# Sensor_Overview.net
KiCad netlist of a schematic drawn in Altium Designer
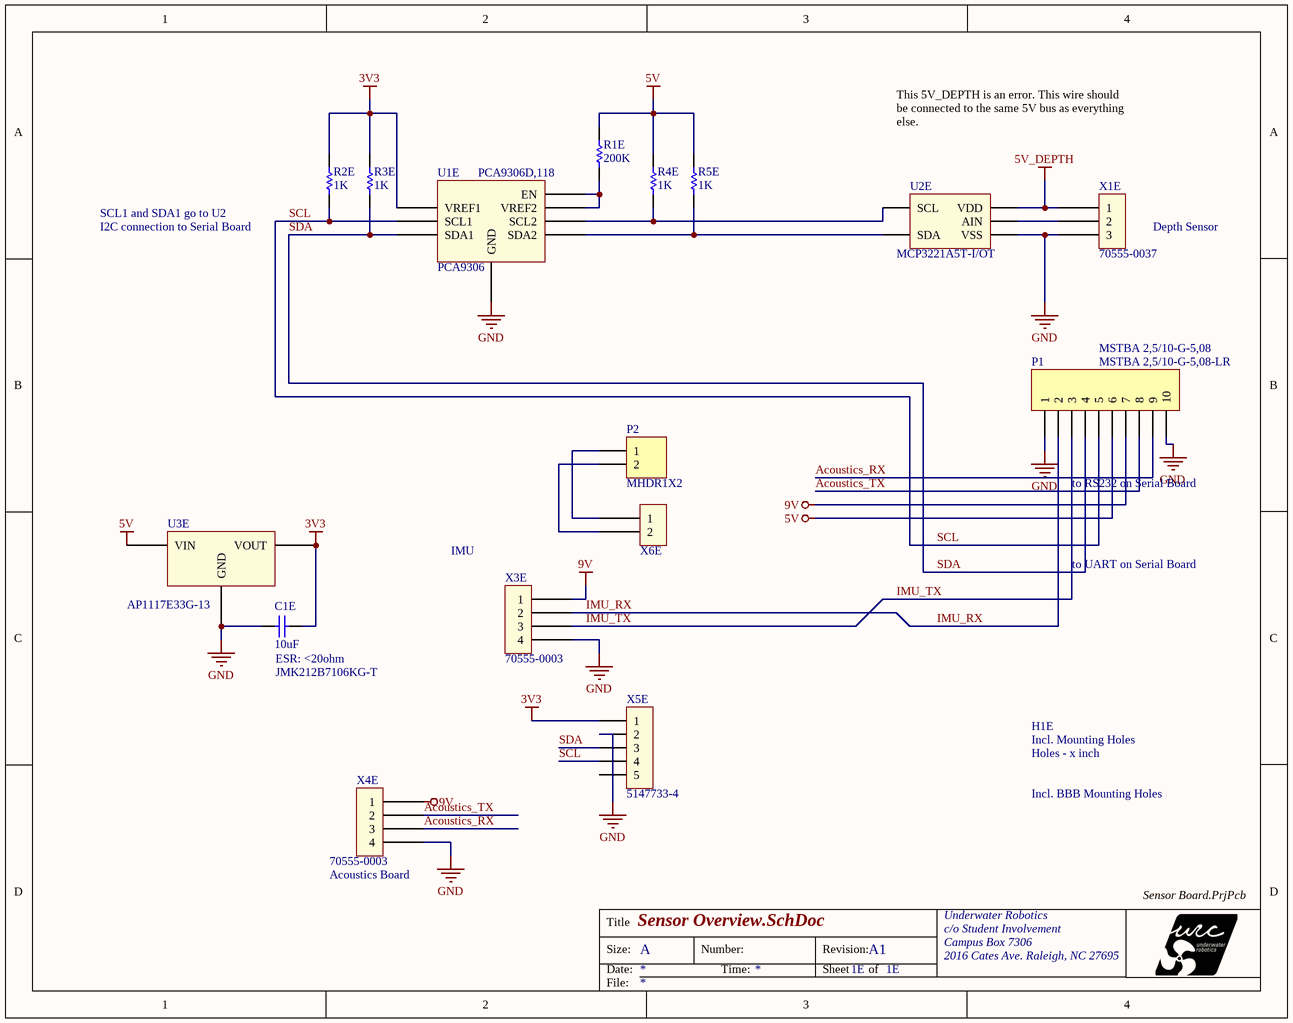
[diagram p0: Sensor Overview.SchDoc]

(export (version "E")
  (design (tool "Eeschema 10.0.6"))
  (components
    (comp (ref "C1E")
      (value "10uF")
      (footprint "C0805")
      (description "Unpolarized Capacitor")
      (fields
        (field (name "ESR") "<20ohm")
        (field (name "MANUFACTURER PART NUMBER") "JMK212B7106KG-T")
        (field (name "Comment") ".1uF")
      )
      (libsource (lib "URC_Lib") (part "Cap"))
    )
    (comp (ref "H1E")
      (value "Holes - x inch")
      (footprint "110mil Holes - 1.0 Inch")
      (libsource (lib "URC") (part "Holes - x inch"))
    )
    (comp (ref "H2E")
      (value "BBB Hole Pattern")
      (footprint "BBB Hole Pattern")
      (libsource (lib "URC") (part "BBB Hole Pattern"))
    )
    (comp (ref "P1")
      (value "MSTBA 2,5/10-G-5,08")
      (footprint "MSTBA 2,5/10-G-5,08")
      (description "Header, 10-Pin")
      (fields (field (name "MANUFACTURER PART NUMBER") "MSTBA 2,5/10-G-5,08-LR"))
      (libsource (lib "Pheonix Contact") (part "MSTBA 2,5/10-G-5,08"))
    )
    (comp (ref "P2")
      (value "MHDR1X2")
      (footprint "MHDR1X2")
      (description "Header, 2-Pin")
      (fields (field (name "PUBLISHER") "Altium Limited"))
      (libsource (lib "Miscellaneous Connectors") (part "MHDR1X2"))
    )
    (comp (ref "R1E")
      (value "200K")
      (footprint "R0603")
      (description "Resistor")
      (fields (field (name "TOLERANCE") "5%") (field (name "MANUFACTURER PART NUMBER") "RC0603JR-07200KL"))
      (libsource (lib "Resistors SchLib") (part "200K, 5%, 100mW, Yageo, R0603"))
    )
    (comp (ref "R2E")
      (value "1K")
      (footprint "R0603")
      (description "Resistor")
      (fields (field (name "TOLERANCE") "5%") (field (name "MANUFACTURER PART NUMBER") "RC0603JR-131KL"))
      (libsource (lib "Resistors SchLib") (part "1k, 5%, 100mW, Yageo, R0603"))
    )
    (comp (ref "R3E")
      (value "1K")
      (footprint "R0603")
      (description "Resistor")
      (fields (field (name "TOLERANCE") "5%") (field (name "MANUFACTURER PART NUMBER") "RC0603JR-131KL"))
      (libsource (lib "Resistors SchLib") (part "1k, 5%, 100mW, Yageo, R0603"))
    )
    (comp (ref "R4E")
      (value "1K")
      (footprint "R0603")
      (description "Resistor")
      (fields (field (name "TOLERANCE") "5%") (field (name "MANUFACTURER PART NUMBER") "RC0603JR-131KL"))
      (libsource (lib "Resistors SchLib") (part "1k, 5%, 100mW, Yageo, R0603"))
    )
    (comp (ref "R5E")
      (value "1K")
      (footprint "R0603")
      (description "Resistor")
      (fields (field (name "TOLERANCE") "5%") (field (name "MANUFACTURER PART NUMBER") "RC0603JR-131KL"))
      (libsource (lib "Resistors SchLib") (part "1k, 5%, 100mW, Yageo, R0603"))
    )
    (comp (ref "U1E")
      (value "PCA9306")
      (footprint "PCA9306-SO8")
      (description "PCA9306, Bidirectional level translator")
      (fields (field (name "MANUFACTURER") "NXP") (field (name "MANUFACTURER PART NUMBER") "PCA9306D,118"))
      (libsource (lib "URC") (part "PCA9306"))
    )
    (comp (ref "U2E")
      (value "~")
      (footprint "MCP3221-SOT23-5")
      (description "MCP3221, 12 bit ADC, I2C")
      (fields
        (field (name "MANUFACTURER") "MICROCHIP")
        (field (name "MANUFACTURER PART NUMBER") "MCP3221A5T-I/OT")
      )
      (libsource (lib "URC") (part "MCP3221"))
    )
    (comp (ref "U3E")
      (value "AP1117E33G-13")
      (footprint "AP1117")
      (description "3.3V 1A Linear Regulator")
      (libsource (lib "URC") (part "AP1117E33G-13"))
    )
    (comp (ref "X1E")
      (value "70555-0037")
      (footprint "70555-0037")
      (description "Molex, C-Grid SL 70555, 3 Pin")
      (fields (field (name "MANUFACTURER") "MOLEX"))
      (libsource (lib "URC") (part "70555-0037"))
    )
    (comp (ref "X3E")
      (value "70555-0003")
      (footprint "70555-0003")
      (description "Molex, C-Grid SL 70555, 4 Pin")
      (fields (field (name "MANUFACTURER") "MOLEX"))
      (libsource (lib "URC") (part "70555-0003"))
    )
    (comp (ref "X4E")
      (value "70555-0003")
      (footprint "70555-0003")
      (description "Molex, C-Grid SL 70555, 4 Pin")
      (fields (field (name "MANUFACTURER") "MOLEX"))
      (libsource (lib "URC") (part "70555-0003"))
    )
    (comp (ref "X5E")
      (value "Header")
      (footprint "SMD Female Header, 5147733-4 w/ header")
      (description "1x5 Header")
      (fields (field (name "MANUFACTURER PART NUMBER") "5147733-4"))
      (libsource (lib "URC") (part "1x5 Header, Female, TE Connectivity"))
    )
    (comp (ref "X6E")
      (value "Header")
      (footprint "1x2 Header")
      (description "1x2 Header")
      (libsource (lib "URC_Lib") (part "1x2 Header"))
    )
  )
  (nets
    (net (code "1") (name "/Acoustics_RX") (class "Default")
      (node (ref "P1") (pin "9") (pinfunction "9_9") (pintype "passive"))
      (node (ref "X4E") (pin "3") (pinfunction "3_3") (pintype "passive"))
    )
    (net (code "2") (name "/Acoustics_TX") (class "Default")
      (node (ref "P1") (pin "8") (pinfunction "8_8") (pintype "passive"))
      (node (ref "X4E") (pin "2") (pinfunction "2_2") (pintype "passive"))
    )
    (net (code "3") (name "/IMU_RX") (class "Default")
      (node (ref "P1") (pin "2") (pinfunction "2_2") (pintype "passive"))
      (node (ref "X3E") (pin "2") (pinfunction "2_2") (pintype "passive"))
    )
    (net (code "4") (name "/IMU_TX") (class "Default")
      (node (ref "P1") (pin "3") (pinfunction "3_3") (pintype "passive"))
      (node (ref "X3E") (pin "3") (pinfunction "3_3") (pintype "passive"))
    )
    (net (code "5") (name "/SCL") (class "Default")
      (node (ref "P1") (pin "5") (pinfunction "5_5") (pintype "passive"))
      (node (ref "R2E") (pin "1") (pinfunction "1_1") (pintype "passive"))
      (node (ref "U1E") (pin "SCL1") (pinfunction "SCL1_SCL1") (pintype "passive"))
      (node (ref "X5E") (pin "4") (pinfunction "4_4") (pintype "passive"))
    )
    (net (code "6") (name "/SDA") (class "Default")
      (node (ref "P1") (pin "4") (pinfunction "4_4") (pintype "passive"))
      (node (ref "R3E") (pin "1") (pinfunction "1_1") (pintype "passive"))
      (node (ref "U1E") (pin "SDA1") (pinfunction "SDA1_SDA1") (pintype "passive"))
      (node (ref "X5E") (pin "3") (pinfunction "3_3") (pintype "passive"))
    )
    (net (code "7") (name "3V3") (class "Default")
      (node (ref "C1E") (pin "1") (pinfunction "1_1") (pintype "passive"))
      (node (ref "R2E") (pin "2") (pinfunction "2_2") (pintype "passive"))
      (node (ref "R3E") (pin "2") (pinfunction "2_2") (pintype "passive"))
      (node (ref "U1E") (pin "VREF1") (pinfunction "VREF1_VREF1") (pintype "passive"))
      (node (ref "U3E") (pin "VOUT") (pinfunction "VOUT_VOUT") (pintype "passive"))
      (node (ref "X5E") (pin "1") (pinfunction "1_1") (pintype "passive"))
    )
    (net (code "8") (name "5V") (class "Default")
      (node (ref "P1") (pin "6") (pinfunction "6_6") (pintype "passive"))
      (node (ref "R1E") (pin "2") (pinfunction "2_2") (pintype "passive"))
      (node (ref "R4E") (pin "2") (pinfunction "2_2") (pintype "passive"))
      (node (ref "R5E") (pin "2") (pinfunction "2_2") (pintype "passive"))
      (node (ref "U3E") (pin "VIN") (pinfunction "VIN_VIN") (pintype "passive"))
    )
    (net (code "9") (name "5V_DEPTH") (class "Default")
      (node (ref "U2E") (pin "VDD") (pinfunction "VDD_VDD") (pintype "passive"))
      (node (ref "X1E") (pin "1") (pinfunction "1_1") (pintype "passive"))
    )
    (net (code "10") (name "9V") (class "Default")
      (node (ref "P1") (pin "7") (pinfunction "7_7") (pintype "passive"))
      (node (ref "X3E") (pin "1") (pinfunction "1_1") (pintype "passive"))
      (node (ref "X4E") (pin "1") (pinfunction "1_1") (pintype "passive"))
    )
    (net (code "11") (name "GND") (class "Default")
      (node (ref "C1E") (pin "2") (pinfunction "2_2") (pintype "passive"))
      (node (ref "P1") (pin "1") (pinfunction "1_1") (pintype "passive"))
      (node (ref "P1") (pin "10") (pinfunction "10_10") (pintype "passive"))
      (node (ref "U1E") (pin "GND") (pinfunction "GND_GND") (pintype "passive"))
      (node (ref "U2E") (pin "VSS") (pinfunction "VSS_VSS") (pintype "passive"))
      (node (ref "U3E") (pin "GND") (pinfunction "GND_GND") (pintype "passive"))
      (node (ref "X1E") (pin "3") (pinfunction "3_3") (pintype "passive"))
      (node (ref "X3E") (pin "4") (pinfunction "4_4") (pintype "passive"))
      (node (ref "X4E") (pin "4") (pinfunction "4_4") (pintype "passive"))
      (node (ref "X5E") (pin "2") (pinfunction "2_2") (pintype "passive"))
    )
    (net (code "12") (name "Net-(P2-Pad1)") (class "Default")
      (node (ref "P2") (pin "1") (pinfunction "1_1") (pintype "passive"))
      (node (ref "X6E") (pin "1") (pinfunction "1_1") (pintype "passive"))
    )
    (net (code "13") (name "Net-(P2-Pad2)") (class "Default")
      (node (ref "P2") (pin "2") (pinfunction "2_2") (pintype "passive"))
      (node (ref "X6E") (pin "2") (pinfunction "2_2") (pintype "passive"))
    )
    (net (code "14") (name "Net-(R1E-Pad1)") (class "Default")
      (node (ref "R1E") (pin "1") (pinfunction "1_1") (pintype "passive"))
      (node (ref "U1E") (pin "EN") (pinfunction "EN_EN") (pintype "passive"))
      (node (ref "U1E") (pin "VREF2") (pinfunction "VREF2_VREF2") (pintype "passive"))
    )
    (net (code "15") (name "Net-(R4E-Pad1)") (class "Default")
      (node (ref "R4E") (pin "1") (pinfunction "1_1") (pintype "passive"))
      (node (ref "U1E") (pin "SCL2") (pinfunction "SCL2_SCL2") (pintype "passive"))
      (node (ref "U2E") (pin "SCL") (pinfunction "SCL_SCL") (pintype "passive"))
    )
    (net (code "16") (name "Net-(R5E-Pad1)") (class "Default")
      (node (ref "R5E") (pin "1") (pinfunction "1_1") (pintype "passive"))
      (node (ref "U1E") (pin "SDA2") (pinfunction "SDA2_SDA2") (pintype "passive"))
      (node (ref "U2E") (pin "SDA") (pinfunction "SDA_SDA") (pintype "passive"))
    )
    (net (code "17") (name "Net-(U2E-PadAIN)") (class "Default")
      (node (ref "U2E") (pin "AIN") (pinfunction "AIN_AIN") (pintype "passive"))
      (node (ref "X1E") (pin "2") (pinfunction "2_2") (pintype "passive"))
    )
    (net (code "18") (name "unconnected-(X5E-Pad5)") (class "Default")
      (node (ref "X5E") (pin "5") (pinfunction "5_5") (pintype "passive"))
    )
  )
)
